# Panel2.net
KiCad netlist of a schematic drawn in EAGLE
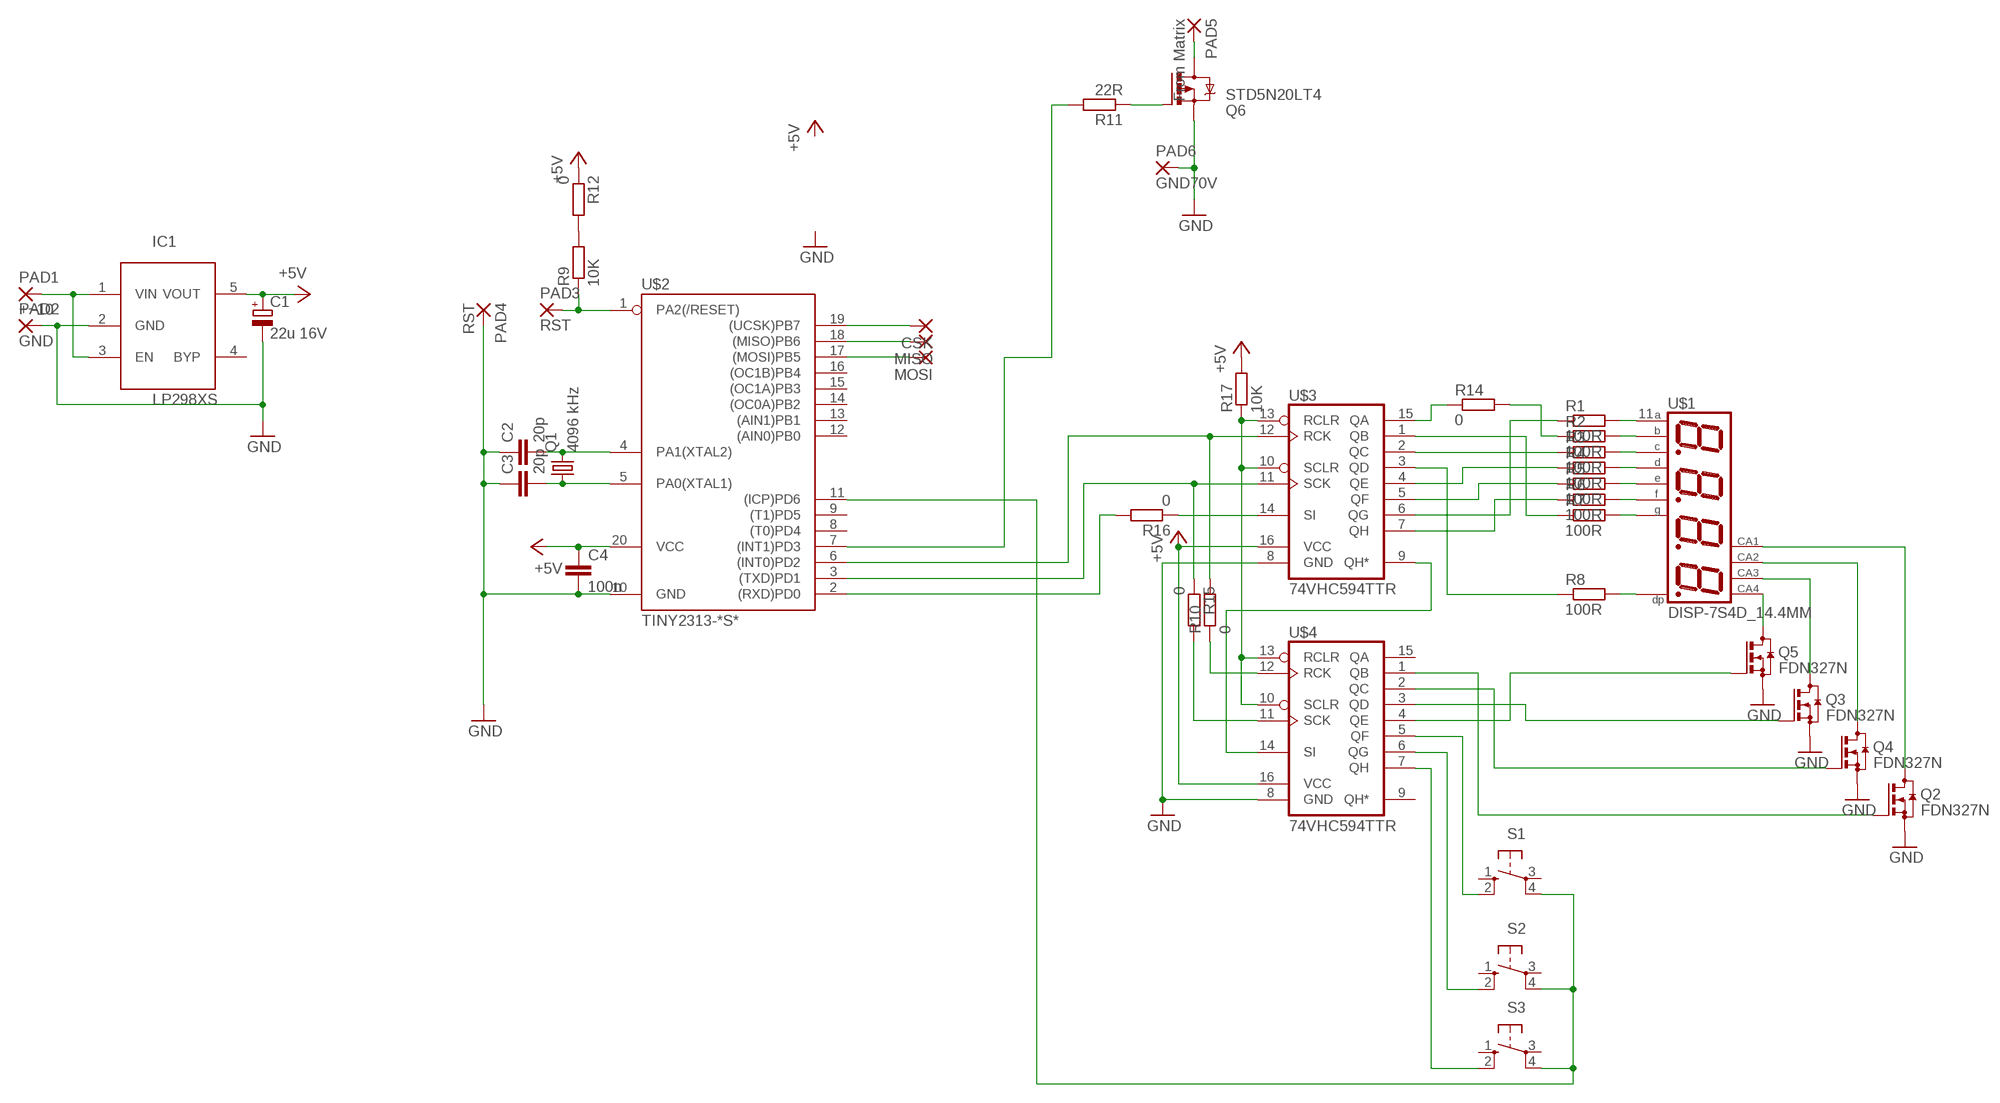
[diagram p0: schematic, sheet 1]

(export (version "E")
  (design (tool "Eeschema 10.0.6"))
  (components
    (comp (ref "C1")
      (value "22u 16V")
      (footprint "eagle-import:SMC_B")
      (libsource (lib "eagle-import") (part "CPOL-EUSMCB"))
    )
    (comp (ref "C2")
      (value "20p")
      (footprint "eagle-import:C1206")
      (libsource (lib "eagle-import") (part "C-EUC1206"))
    )
    (comp (ref "C3")
      (value "20p")
      (footprint "eagle-import:C1206")
      (libsource (lib "eagle-import") (part "C-EUC1206"))
    )
    (comp (ref "C4")
      (value "100n")
      (footprint "eagle-import:C1206")
      (libsource (lib "eagle-import") (part "C-EUC1206"))
    )
    (comp (ref "CSK")
      (value "SMD2")
      (footprint "eagle-import:SMD1,27-2,54")
      (libsource (lib "eagle-import") (part "SMD2"))
    )
    (comp (ref "IC1")
      (value "LP298XS")
      (footprint "eagle-import:SOT23-5L")
      (libsource (lib "eagle-import") (part "LP298XS"))
    )
    (comp (ref "MISO")
      (value "SMD2")
      (footprint "eagle-import:SMD1,27-2,54")
      (libsource (lib "eagle-import") (part "SMD2"))
    )
    (comp (ref "MOSI")
      (value "SMD2")
      (footprint "eagle-import:SMD1,27-2,54")
      (libsource (lib "eagle-import") (part "SMD2"))
    )
    (comp (ref "PAD1")
      (value "+~10")
      (footprint "eagle-import:5-2,5")
      (libsource (lib "eagle-import") (part "WIREPADSMD5-2,5"))
    )
    (comp (ref "PAD2")
      (value "GND")
      (footprint "eagle-import:5-2,5")
      (libsource (lib "eagle-import") (part "WIREPADSMD5-2,5"))
    )
    (comp (ref "PAD3")
      (value "RST")
      (footprint "eagle-import:SMD1,27-2,54")
      (libsource (lib "eagle-import") (part "WIREPADSMD1,27-254"))
    )
    (comp (ref "PAD4")
      (value "RST")
      (footprint "eagle-import:SMD1,27-2,54")
      (libsource (lib "eagle-import") (part "WIREPADSMD1,27-254"))
    )
    (comp (ref "PAD5")
      (value "From Matrix")
      (footprint "eagle-import:SMD2,54-5,08")
      (libsource (lib "eagle-import") (part "WIREPADSMD2,54-5,08"))
    )
    (comp (ref "PAD6")
      (value "GND70V")
      (footprint "eagle-import:SMD2,54-5,08")
      (libsource (lib "eagle-import") (part "WIREPADSMD2,54-5,08"))
    )
    (comp (ref "Q1")
      (value "4096 kHz")
      (footprint "eagle-import:HC49U-V")
      (libsource (lib "eagle-import") (part "CRYSTALHC49U-V"))
    )
    (comp (ref "Q2")
      (value "FDN327N")
      (footprint "eagle-import:SOT23")
      (libsource (lib "eagle-import") (part "BSS123"))
    )
    (comp (ref "Q3")
      (value "FDN327N")
      (footprint "eagle-import:SOT23")
      (libsource (lib "eagle-import") (part "BSS123"))
    )
    (comp (ref "Q4")
      (value "FDN327N")
      (footprint "eagle-import:SOT23")
      (libsource (lib "eagle-import") (part "BSS123"))
    )
    (comp (ref "Q5")
      (value "FDN327N")
      (footprint "eagle-import:SOT23")
      (libsource (lib "eagle-import") (part "BSS123"))
    )
    (comp (ref "Q6")
      (value "STD5N20LT4")
      (footprint "eagle-import:D-PAK_TO252AA")
      (libsource (lib "eagle-import") (part "IRF?5305R"))
    )
    (comp (ref "R1")
      (value "100R")
      (footprint "eagle-import:R1206")
      (libsource (lib "eagle-import") (part "R-EU_R1206"))
    )
    (comp (ref "R2")
      (value "100R")
      (footprint "eagle-import:R1206")
      (libsource (lib "eagle-import") (part "R-EU_R1206"))
    )
    (comp (ref "R3")
      (value "100R")
      (footprint "eagle-import:R1206")
      (libsource (lib "eagle-import") (part "R-EU_R1206"))
    )
    (comp (ref "R4")
      (value "100R")
      (footprint "eagle-import:R1206")
      (libsource (lib "eagle-import") (part "R-EU_R1206"))
    )
    (comp (ref "R5")
      (value "100R")
      (footprint "eagle-import:R1206")
      (libsource (lib "eagle-import") (part "R-EU_R1206"))
    )
    (comp (ref "R6")
      (value "100R")
      (footprint "eagle-import:R1206")
      (libsource (lib "eagle-import") (part "R-EU_R1206"))
    )
    (comp (ref "R7")
      (value "100R")
      (footprint "eagle-import:R1206")
      (libsource (lib "eagle-import") (part "R-EU_R1206"))
    )
    (comp (ref "R8")
      (value "100R")
      (footprint "eagle-import:R1206")
      (libsource (lib "eagle-import") (part "R-EU_R1206"))
    )
    (comp (ref "R9")
      (value "10K")
      (footprint "eagle-import:R1206")
      (libsource (lib "eagle-import") (part "R-EU_R1206"))
    )
    (comp (ref "R10")
      (value "0")
      (footprint "eagle-import:R1206")
      (libsource (lib "eagle-import") (part "R-EU_R1206"))
    )
    (comp (ref "R11")
      (value "22R")
      (footprint "eagle-import:R1206")
      (libsource (lib "eagle-import") (part "R-EU_R1206"))
    )
    (comp (ref "R12")
      (value "0")
      (footprint "eagle-import:R1206")
      (libsource (lib "eagle-import") (part "R-EU_R1206"))
    )
    (comp (ref "R14")
      (value "0")
      (footprint "eagle-import:R1206")
      (libsource (lib "eagle-import") (part "R-EU_R1206"))
    )
    (comp (ref "R15")
      (value "0")
      (footprint "eagle-import:R1206")
      (libsource (lib "eagle-import") (part "R-EU_R1206"))
    )
    (comp (ref "R16")
      (value "0")
      (footprint "eagle-import:R1206")
      (libsource (lib "eagle-import") (part "R-EU_R1206"))
    )
    (comp (ref "R17")
      (value "10K")
      (footprint "eagle-import:R1206")
      (libsource (lib "eagle-import") (part "R-EU_R1206"))
    )
    (comp (ref "S1")
      (value "40-XX")
      (footprint "eagle-import:B3F-40XX")
      (fields (field (name "MF") "OMRON COMPONENTS USA") (field (name "MPN") "B3F-4000"))
      (libsource (lib "eagle-import") (part "40-XX"))
    )
    (comp (ref "S2")
      (value "40-XX")
      (footprint "eagle-import:B3F-40XX")
      (fields (field (name "MF") "OMRON COMPONENTS USA") (field (name "MPN") "B3F-4000"))
      (libsource (lib "eagle-import") (part "40-XX"))
    )
    (comp (ref "S3")
      (value "40-XX")
      (footprint "eagle-import:B3F-40XX")
      (fields (field (name "MF") "OMRON COMPONENTS USA") (field (name "MPN") "B3F-4000"))
      (libsource (lib "eagle-import") (part "40-XX"))
    )
    (comp (ref "U$1")
      (value "DISP-7S4D_14.4MM")
      (footprint "eagle-import:DISP-7S4D")
      (libsource (lib "eagle-import") (part "DISP-7S4D_14.4MM"))
    )
    (comp (ref "U$2")
      (value "TINY2313-*S*")
      (footprint "eagle-import:SO20L$")
      (libsource (lib "eagle-import") (part "TINY2313-S"))
    )
    (comp (ref "U$3")
      (value "74VHC594TTR")
      (footprint "eagle-import:TSSOP16")
      (libsource (lib "eagle-import") (part "74VHC594TTR"))
    )
    (comp (ref "U$4")
      (value "74VHC594TTR")
      (footprint "eagle-import:TSSOP16")
      (libsource (lib "eagle-import") (part "74VHC594TTR"))
    )
  )
  (nets
    (net (code "1") (name "+5V") (class "Default")
      (node (ref "C1") (pin "+") (pinfunction "+_+") (pintype "passive"))
      (node (ref "C4") (pin "1") (pinfunction "1_1") (pintype "passive"))
      (node (ref "IC1") (pin "5") (pinfunction "VOUT_5") (pintype "bidirectional"))
      (node (ref "R12") (pin "1") (pinfunction "1_1") (pintype "passive"))
      (node (ref "R17") (pin "2") (pinfunction "2_2") (pintype "passive"))
      (node (ref "U$2") (pin "20") (pinfunction "VCC_20") (pintype "power_in"))
      (node (ref "U$3") (pin "16") (pinfunction "VCC_16") (pintype "bidirectional"))
      (node (ref "U$4") (pin "16") (pinfunction "VCC_16") (pintype "bidirectional"))
    )
    (net (code "2") (name "GND") (class "Default")
      (node (ref "C1") (pin "-") (pinfunction "-_-") (pintype "passive"))
      (node (ref "C2") (pin "1") (pinfunction "1_1") (pintype "passive"))
      (node (ref "C3") (pin "1") (pinfunction "1_1") (pintype "passive"))
      (node (ref "C4") (pin "2") (pinfunction "2_2") (pintype "passive"))
      (node (ref "IC1") (pin "2") (pinfunction "GND_2") (pintype "bidirectional"))
      (node (ref "PAD2") (pin "1") (pinfunction "P_1") (pintype "passive"))
      (node (ref "PAD4") (pin "1") (pinfunction "P_1") (pintype "passive"))
      (node (ref "PAD6") (pin "1") (pinfunction "P_1") (pintype "passive"))
      (node (ref "Q2") (pin "2") (pinfunction "S_2") (pintype "passive"))
      (node (ref "Q3") (pin "2") (pinfunction "S_2") (pintype "passive"))
      (node (ref "Q4") (pin "2") (pinfunction "S_2") (pintype "passive"))
      (node (ref "Q5") (pin "2") (pinfunction "S_2") (pintype "passive"))
      (node (ref "Q6") (pin "3") (pinfunction "S_3") (pintype "passive"))
      (node (ref "U$2") (pin "10") (pinfunction "GND_10") (pintype "power_in"))
      (node (ref "U$3") (pin "8") (pinfunction "GND_8") (pintype "bidirectional"))
      (node (ref "U$4") (pin "8") (pinfunction "GND_8") (pintype "bidirectional"))
    )
    (net (code "3") (name "Net-(CSK-P)") (class "Default")
      (node (ref "CSK") (pin "1") (pinfunction "P_1") (pintype "passive"))
      (node (ref "U$2") (pin "19") (pinfunction "(UCSK)PB7_19") (pintype "bidirectional"))
    )
    (net (code "4") (name "Net-(IC1-EN)") (class "Default")
      (node (ref "IC1") (pin "1") (pinfunction "VIN_1") (pintype "bidirectional"))
      (node (ref "IC1") (pin "3") (pinfunction "EN_3") (pintype "bidirectional"))
      (node (ref "PAD1") (pin "1") (pinfunction "P_1") (pintype "passive"))
    )
    (net (code "5") (name "Net-(MISO-P)") (class "Default")
      (node (ref "MISO") (pin "1") (pinfunction "P_1") (pintype "passive"))
      (node (ref "U$2") (pin "18") (pinfunction "(MISO)PB6_18") (pintype "bidirectional"))
    )
    (net (code "6") (name "Net-(MOSI-P)") (class "Default")
      (node (ref "MOSI") (pin "1") (pinfunction "P_1") (pintype "passive"))
      (node (ref "U$2") (pin "17") (pinfunction "(MOSI)PB5_17") (pintype "bidirectional"))
    )
    (net (code "7") (name "Net-(PAD3-P)") (class "Default")
      (node (ref "PAD3") (pin "1") (pinfunction "P_1") (pintype "passive"))
      (node (ref "R9") (pin "1") (pinfunction "1_1") (pintype "passive"))
      (node (ref "U$2") (pin "1") (pinfunction "PA2(/RESET)_1") (pintype "input"))
    )
    (net (code "8") (name "Net-(PAD5-P)") (class "Default")
      (node (ref "PAD5") (pin "1") (pinfunction "P_1") (pintype "passive"))
      (node (ref "Q6") (pin "4") (pinfunction "D_4") (pintype "passive"))
    )
    (net (code "9") (name "Net-(Q2-D)") (class "Default")
      (node (ref "Q2") (pin "3") (pinfunction "D_3") (pintype "passive"))
      (node (ref "U$1") (pin "12") (pinfunction "С1_12") (pintype "bidirectional"))
    )
    (net (code "10") (name "Net-(Q2-G)") (class "Default")
      (node (ref "Q2") (pin "1") (pinfunction "G_1") (pintype "passive"))
      (node (ref "U$4") (pin "1") (pinfunction "QB_1") (pintype "output"))
    )
    (net (code "11") (name "Net-(Q3-D)") (class "Default")
      (node (ref "Q3") (pin "3") (pinfunction "D_3") (pintype "passive"))
      (node (ref "U$1") (pin "8") (pinfunction "С3_8") (pintype "bidirectional"))
    )
    (net (code "12") (name "Net-(Q3-G)") (class "Default")
      (node (ref "Q3") (pin "1") (pinfunction "G_1") (pintype "passive"))
      (node (ref "U$4") (pin "3") (pinfunction "QD_3") (pintype "output"))
    )
    (net (code "13") (name "Net-(Q4-D)") (class "Default")
      (node (ref "Q4") (pin "3") (pinfunction "D_3") (pintype "passive"))
      (node (ref "U$1") (pin "9") (pinfunction "С2_9") (pintype "bidirectional"))
    )
    (net (code "14") (name "Net-(Q4-G)") (class "Default")
      (node (ref "Q4") (pin "1") (pinfunction "G_1") (pintype "passive"))
      (node (ref "U$4") (pin "2") (pinfunction "QC_2") (pintype "output"))
    )
    (net (code "15") (name "Net-(Q5-D)") (class "Default")
      (node (ref "Q5") (pin "3") (pinfunction "D_3") (pintype "passive"))
      (node (ref "U$1") (pin "6") (pinfunction "С4_6") (pintype "bidirectional"))
    )
    (net (code "16") (name "Net-(Q5-G)") (class "Default")
      (node (ref "Q5") (pin "1") (pinfunction "G_1") (pintype "passive"))
      (node (ref "U$4") (pin "4") (pinfunction "QE_4") (pintype "output"))
    )
    (net (code "17") (name "Net-(Q6-G)") (class "Default")
      (node (ref "Q6") (pin "1") (pinfunction "G_1") (pintype "passive"))
      (node (ref "R11") (pin "1") (pinfunction "1_1") (pintype "passive"))
    )
    (net (code "18") (name "Net-(R12-Pad2)") (class "Default")
      (node (ref "R12") (pin "2") (pinfunction "2_2") (pintype "passive"))
      (node (ref "R9") (pin "2") (pinfunction "2_2") (pintype "passive"))
    )
    (net (code "19") (name "Net-(R14-Pad2)") (class "Default")
      (node (ref "R14") (pin "2") (pinfunction "2_2") (pintype "passive"))
      (node (ref "R2") (pin "1") (pinfunction "1_1") (pintype "passive"))
    )
    (net (code "20") (name "Net-(S1-P1)") (class "Default")
      (node (ref "S1") (pin "4") (pinfunction "P1_4") (pintype "passive"))
      (node (ref "S2") (pin "4") (pinfunction "P1_4") (pintype "passive"))
      (node (ref "S3") (pin "4") (pinfunction "P1_4") (pintype "passive"))
      (node (ref "U$2") (pin "11") (pinfunction "(ICP)PD6_11") (pintype "bidirectional"))
    )
    (net (code "21") (name "Net-(S1-S1)") (class "Default")
      (node (ref "S1") (pin "2") (pinfunction "S1_2") (pintype "passive"))
      (node (ref "U$4") (pin "5") (pinfunction "QF_5") (pintype "output"))
    )
    (net (code "22") (name "Net-(S2-S1)") (class "Default")
      (node (ref "S2") (pin "2") (pinfunction "S1_2") (pintype "passive"))
      (node (ref "U$4") (pin "6") (pinfunction "QG_6") (pintype "output"))
    )
    (net (code "23") (name "Net-(S3-S1)") (class "Default")
      (node (ref "S3") (pin "2") (pinfunction "S1_2") (pintype "passive"))
      (node (ref "U$4") (pin "7") (pinfunction "QH_7") (pintype "output"))
    )
    (net (code "24") (name "Net-(U$1-A)") (class "Default")
      (node (ref "R1") (pin "2") (pinfunction "2_2") (pintype "passive"))
      (node (ref "U$1") (pin "11") (pinfunction "A_11") (pintype "passive"))
    )
    (net (code "25") (name "Net-(U$1-B)") (class "Default")
      (node (ref "R2") (pin "2") (pinfunction "2_2") (pintype "passive"))
      (node (ref "U$1") (pin "7") (pinfunction "B_7") (pintype "passive"))
    )
    (net (code "26") (name "Net-(U$1-C)") (class "Default")
      (node (ref "R3") (pin "2") (pinfunction "2_2") (pintype "passive"))
      (node (ref "U$1") (pin "4") (pinfunction "C_4") (pintype "passive"))
    )
    (net (code "27") (name "Net-(U$1-D)") (class "Default")
      (node (ref "R4") (pin "2") (pinfunction "2_2") (pintype "passive"))
      (node (ref "U$1") (pin "2") (pinfunction "D_2") (pintype "passive"))
    )
    (net (code "28") (name "Net-(U$1-DP)") (class "Default")
      (node (ref "R8") (pin "2") (pinfunction "2_2") (pintype "passive"))
      (node (ref "U$1") (pin "3") (pinfunction "DP_3") (pintype "passive"))
    )
    (net (code "29") (name "Net-(U$1-E)") (class "Default")
      (node (ref "R5") (pin "2") (pinfunction "2_2") (pintype "passive"))
      (node (ref "U$1") (pin "1") (pinfunction "E_1") (pintype "passive"))
    )
    (net (code "30") (name "Net-(U$1-F)") (class "Default")
      (node (ref "R6") (pin "2") (pinfunction "2_2") (pintype "passive"))
      (node (ref "U$1") (pin "10") (pinfunction "F_10") (pintype "passive"))
    )
    (net (code "31") (name "Net-(U$1-G)") (class "Default")
      (node (ref "R7") (pin "2") (pinfunction "2_2") (pintype "passive"))
      (node (ref "U$1") (pin "5") (pinfunction "G_5") (pintype "passive"))
    )
    (net (code "32") (name "Net-(U$2-(INT0)PD2)") (class "Default")
      (node (ref "R10") (pin "2") (pinfunction "2_2") (pintype "passive"))
      (node (ref "U$2") (pin "6") (pinfunction "(INT0)PD2_6") (pintype "bidirectional"))
      (node (ref "U$3") (pin "12") (pinfunction "RCK_12") (pintype "input"))
    )
    (net (code "33") (name "Net-(U$2-(INT1)PD3)") (class "Default")
      (node (ref "R11") (pin "2") (pinfunction "2_2") (pintype "passive"))
      (node (ref "U$2") (pin "7") (pinfunction "(INT1)PD3_7") (pintype "bidirectional"))
    )
    (net (code "34") (name "Net-(U$2-(RXD)PD0)") (class "Default")
      (node (ref "R16") (pin "2") (pinfunction "2_2") (pintype "passive"))
      (node (ref "U$2") (pin "2") (pinfunction "(RXD)PD0_2") (pintype "bidirectional"))
    )
    (net (code "35") (name "Net-(U$2-(TXD)PD1)") (class "Default")
      (node (ref "R15") (pin "1") (pinfunction "1_1") (pintype "passive"))
      (node (ref "U$2") (pin "3") (pinfunction "(TXD)PD1_3") (pintype "bidirectional"))
      (node (ref "U$3") (pin "11") (pinfunction "SCK_11") (pintype "input"))
    )
    (net (code "36") (name "Net-(U$2-PA0(XTAL1))") (class "Default")
      (node (ref "C3") (pin "2") (pinfunction "2_2") (pintype "passive"))
      (node (ref "Q1") (pin "1") (pinfunction "1_1") (pintype "passive"))
      (node (ref "U$2") (pin "5") (pinfunction "PA0(XTAL1)_5") (pintype "bidirectional"))
    )
    (net (code "37") (name "Net-(U$2-PA1(XTAL2))") (class "Default")
      (node (ref "C2") (pin "2") (pinfunction "2_2") (pintype "passive"))
      (node (ref "Q1") (pin "2") (pinfunction "2_2") (pintype "passive"))
      (node (ref "U$2") (pin "4") (pinfunction "PA1(XTAL2)_4") (pintype "bidirectional"))
    )
    (net (code "38") (name "Net-(U$3-QA)") (class "Default")
      (node (ref "R14") (pin "1") (pinfunction "1_1") (pintype "passive"))
      (node (ref "U$3") (pin "15") (pinfunction "QA_15") (pintype "output"))
    )
    (net (code "39") (name "Net-(U$3-QB)") (class "Default")
      (node (ref "R7") (pin "1") (pinfunction "1_1") (pintype "passive"))
      (node (ref "U$3") (pin "1") (pinfunction "QB_1") (pintype "output"))
    )
    (net (code "40") (name "Net-(U$3-QC)") (class "Default")
      (node (ref "R3") (pin "1") (pinfunction "1_1") (pintype "passive"))
      (node (ref "U$3") (pin "2") (pinfunction "QC_2") (pintype "output"))
    )
    (net (code "41") (name "Net-(U$3-QD)") (class "Default")
      (node (ref "R8") (pin "1") (pinfunction "1_1") (pintype "passive"))
      (node (ref "U$3") (pin "3") (pinfunction "QD_3") (pintype "output"))
    )
    (net (code "42") (name "Net-(U$3-QE)") (class "Default")
      (node (ref "R4") (pin "1") (pinfunction "1_1") (pintype "passive"))
      (node (ref "U$3") (pin "4") (pinfunction "QE_4") (pintype "output"))
    )
    (net (code "43") (name "Net-(U$3-QF)") (class "Default")
      (node (ref "R5") (pin "1") (pinfunction "1_1") (pintype "passive"))
      (node (ref "U$3") (pin "5") (pinfunction "QF_5") (pintype "output"))
    )
    (net (code "44") (name "Net-(U$3-QG)") (class "Default")
      (node (ref "R1") (pin "1") (pinfunction "1_1") (pintype "passive"))
      (node (ref "U$3") (pin "6") (pinfunction "QG_6") (pintype "output"))
    )
    (net (code "45") (name "Net-(U$3-QH)") (class "Default")
      (node (ref "R6") (pin "1") (pinfunction "1_1") (pintype "passive"))
      (node (ref "U$3") (pin "7") (pinfunction "QH_7") (pintype "output"))
    )
    (net (code "46") (name "Net-(U$3-QH*)") (class "Default")
      (node (ref "U$3") (pin "9") (pinfunction "QH*_9") (pintype "output"))
      (node (ref "U$4") (pin "14") (pinfunction "SI_14") (pintype "input"))
    )
    (net (code "47") (name "Net-(U$3-RCLR)") (class "Default")
      (node (ref "R17") (pin "1") (pinfunction "1_1") (pintype "passive"))
      (node (ref "U$3") (pin "10") (pinfunction "SCLR_10") (pintype "input"))
      (node (ref "U$3") (pin "13") (pinfunction "RCLR_13") (pintype "input"))
      (node (ref "U$4") (pin "10") (pinfunction "SCLR_10") (pintype "input"))
      (node (ref "U$4") (pin "13") (pinfunction "RCLR_13") (pintype "input"))
    )
    (net (code "48") (name "Net-(U$3-SI)") (class "Default")
      (node (ref "R16") (pin "1") (pinfunction "1_1") (pintype "passive"))
      (node (ref "U$3") (pin "14") (pinfunction "SI_14") (pintype "input"))
    )
    (net (code "49") (name "Net-(U$4-RCK)") (class "Default")
      (node (ref "R10") (pin "1") (pinfunction "1_1") (pintype "passive"))
      (node (ref "U$4") (pin "12") (pinfunction "RCK_12") (pintype "input"))
    )
    (net (code "50") (name "Net-(U$4-SCK)") (class "Default")
      (node (ref "R15") (pin "2") (pinfunction "2_2") (pintype "passive"))
      (node (ref "U$4") (pin "11") (pinfunction "SCK_11") (pintype "input"))
    )
    (net (code "51") (name "unconnected-(IC1-BYP-Pad4)") (class "Default")
      (node (ref "IC1") (pin "4") (pinfunction "BYP_4") (pintype "bidirectional"))
    )
    (net (code "52") (name "unconnected-(S1-P-Pad3)") (class "Default")
      (node (ref "S1") (pin "3") (pinfunction "P_3") (pintype "passive"))
    )
    (net (code "53") (name "unconnected-(S1-S-Pad1)") (class "Default")
      (node (ref "S1") (pin "1") (pinfunction "S_1") (pintype "passive"))
    )
    (net (code "54") (name "unconnected-(S2-P-Pad3)") (class "Default")
      (node (ref "S2") (pin "3") (pinfunction "P_3") (pintype "passive"))
    )
    (net (code "55") (name "unconnected-(S2-S-Pad1)") (class "Default")
      (node (ref "S2") (pin "1") (pinfunction "S_1") (pintype "passive"))
    )
    (net (code "56") (name "unconnected-(S3-P-Pad3)") (class "Default")
      (node (ref "S3") (pin "3") (pinfunction "P_3") (pintype "passive"))
    )
    (net (code "57") (name "unconnected-(S3-S-Pad1)") (class "Default")
      (node (ref "S3") (pin "1") (pinfunction "S_1") (pintype "passive"))
    )
    (net (code "58") (name "unconnected-(U$2-(AIN0)PB0-Pad12)") (class "Default")
      (node (ref "U$2") (pin "12") (pinfunction "(AIN0)PB0_12") (pintype "bidirectional"))
    )
    (net (code "59") (name "unconnected-(U$2-(AIN1)PB1-Pad13)") (class "Default")
      (node (ref "U$2") (pin "13") (pinfunction "(AIN1)PB1_13") (pintype "bidirectional"))
    )
    (net (code "60") (name "unconnected-(U$2-(OC0A)PB2-Pad14)") (class "Default")
      (node (ref "U$2") (pin "14") (pinfunction "(OC0A)PB2_14") (pintype "bidirectional"))
    )
    (net (code "61") (name "unconnected-(U$2-(OC1A)PB3-Pad15)") (class "Default")
      (node (ref "U$2") (pin "15") (pinfunction "(OC1A)PB3_15") (pintype "bidirectional"))
    )
    (net (code "62") (name "unconnected-(U$2-(OC1B)PB4-Pad16)") (class "Default")
      (node (ref "U$2") (pin "16") (pinfunction "(OC1B)PB4_16") (pintype "bidirectional"))
    )
    (net (code "63") (name "unconnected-(U$2-(T0)PD4-Pad8)") (class "Default")
      (node (ref "U$2") (pin "8") (pinfunction "(T0)PD4_8") (pintype "bidirectional"))
    )
    (net (code "64") (name "unconnected-(U$2-(T1)PD5-Pad9)") (class "Default")
      (node (ref "U$2") (pin "9") (pinfunction "(T1)PD5_9") (pintype "bidirectional"))
    )
    (net (code "65") (name "unconnected-(U$4-QA-Pad15)") (class "Default")
      (node (ref "U$4") (pin "15") (pinfunction "QA_15") (pintype "output"))
    )
    (net (code "66") (name "unconnected-(U$4-QH*-Pad9)") (class "Default")
      (node (ref "U$4") (pin "9") (pinfunction "QH*_9") (pintype "output"))
    )
  )
)
